# AIRDCL.net
KiCad netlist of a schematic drawn in EAGLE
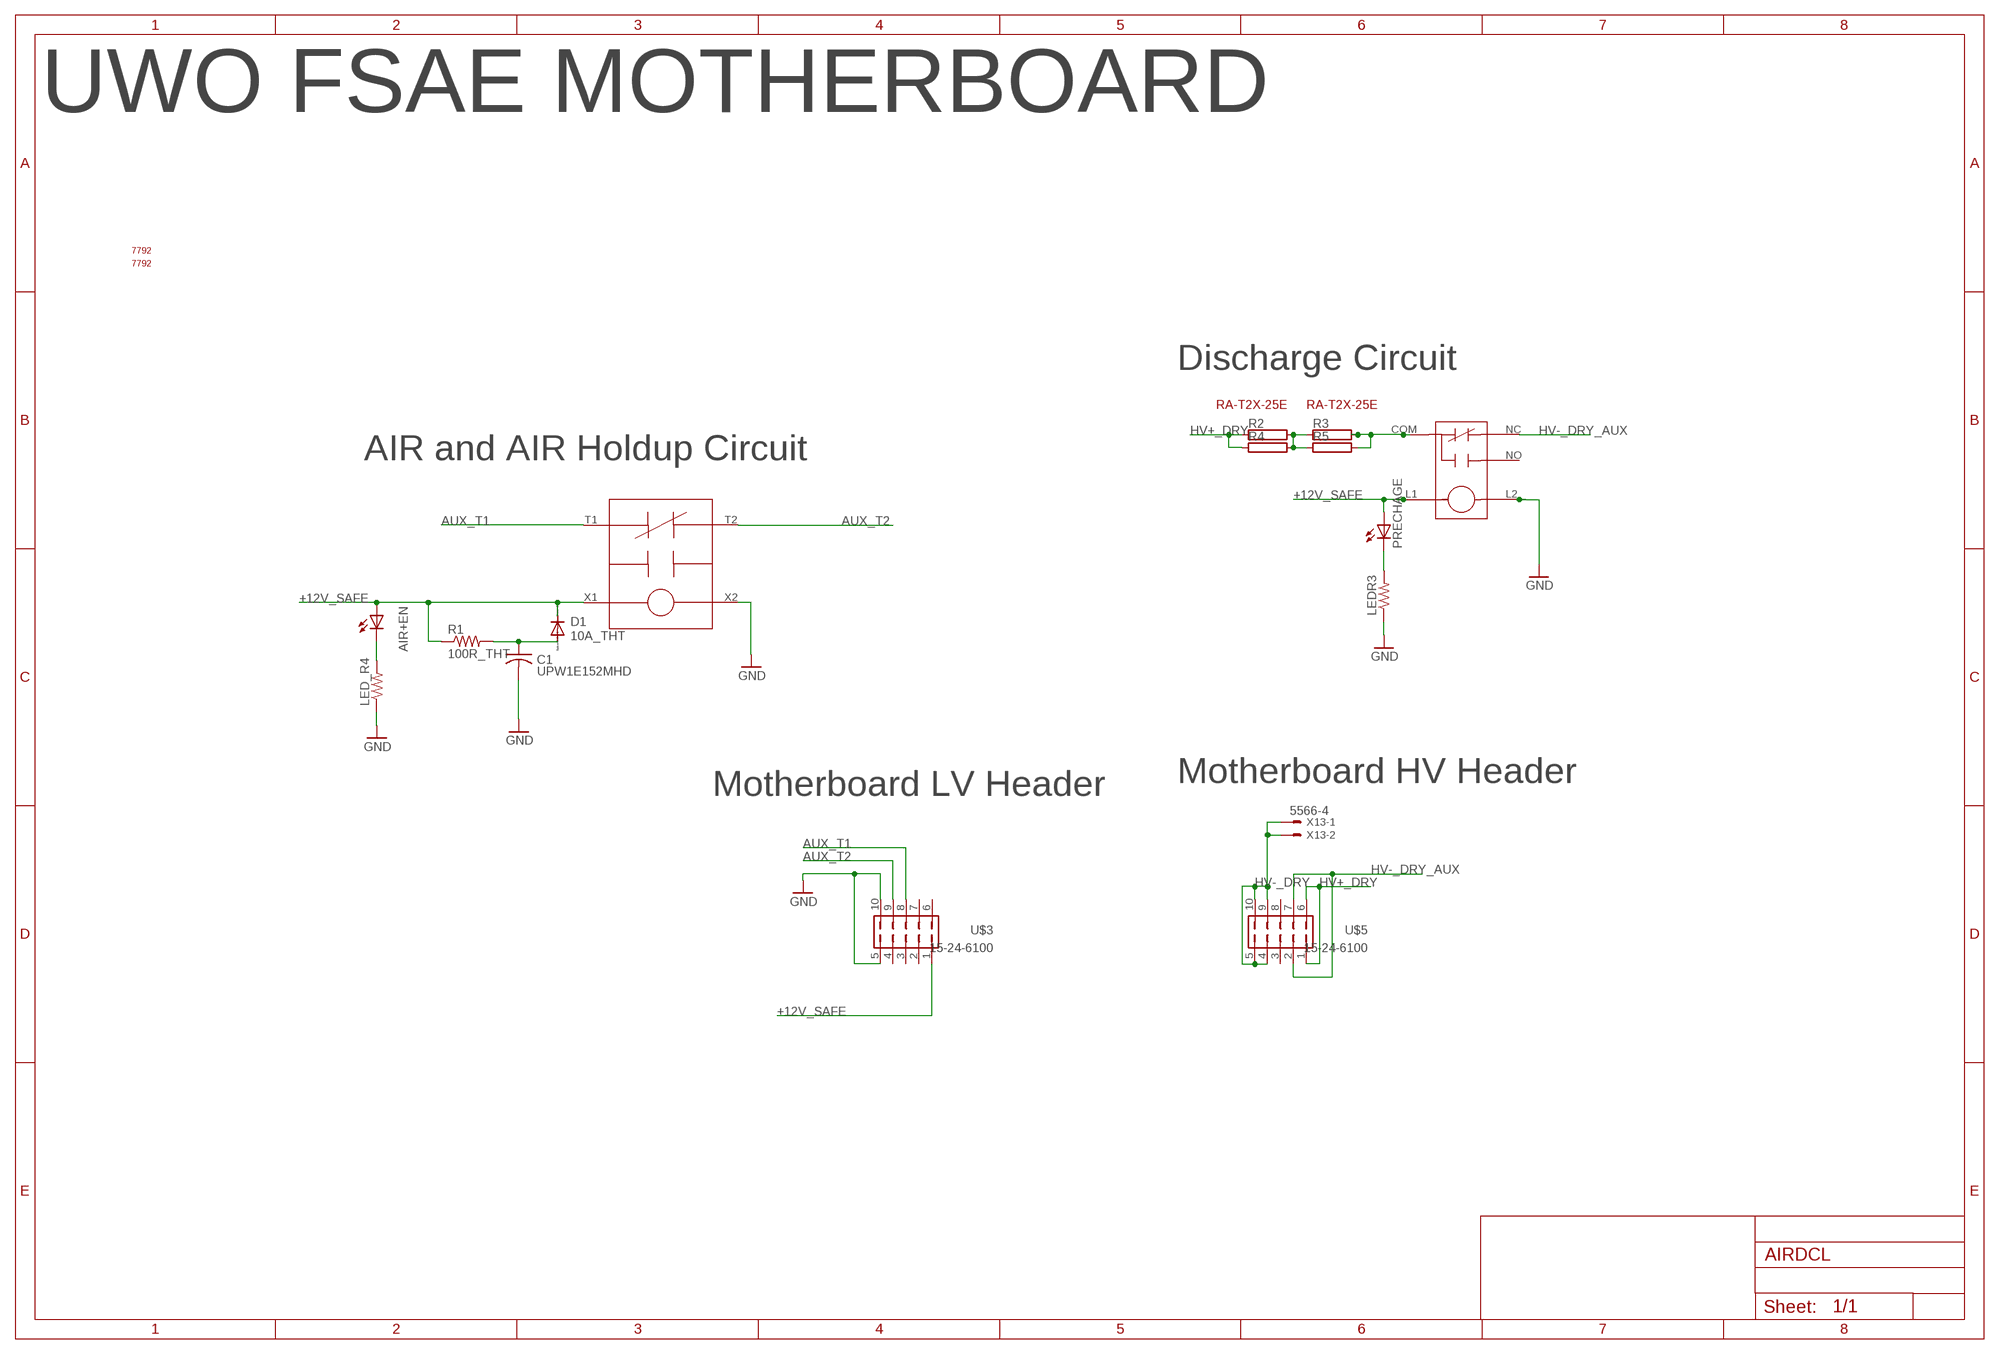
[diagram p0: schematic, sheet 1]

(export (version "E")
  (design (tool "Eeschema 10.0.6"))
  (components
    (comp (ref "AIR+EN")
      (value "LEDCHIPLED_0805")
      (footprint "eagle-import:CHIPLED_0805")
      (libsource (lib "eagle-import") (part "LEDCHIPLED_0805"))
    )
    (comp (ref "C1")
      (value "UPW1E152MHD")
      (footprint "eagle-import:CAPPRD750W65D1800H3700B")
      (libsource (lib "eagle-import") (part "AIR_HOLDUP_CAP"))
    )
    (comp (ref "D1")
      (value "10A_THT")
      (footprint "eagle-import:DIOAD1570W120L850D500B")
      (libsource (lib "eagle-import") (part "AIR_HOLDUP_DIODE"))
    )
    (comp (ref "LEDR3")
      (value "R-US_R0805")
      (footprint "eagle-import:R0805")
      (libsource (lib "eagle-import") (part "R-US_R0805"))
    )
    (comp (ref "LED_R4")
      (value "R-US_R0805")
      (footprint "eagle-import:R0805")
      (libsource (lib "eagle-import") (part "R-US_R0805"))
    )
    (comp (ref "PRECHAGE")
      (value "LEDCHIPLED_0805")
      (footprint "eagle-import:CHIPLED_0805")
      (libsource (lib "eagle-import") (part "LEDCHIPLED_0805"))
    )
    (comp (ref "R1")
      (value "100R_THT")
      (footprint "eagle-import:RESAD976W63L650D250B")
      (libsource (lib "eagle-import") (part "AIR_HOLDUP_RESISTOR"))
    )
    (comp (ref "R2")
      (value "RMG100-V")
      (footprint "eagle-import:TO-247-2V")
      (libsource (lib "eagle-import") (part "RMG100-V"))
    )
    (comp (ref "R3")
      (value "RMG100-V")
      (footprint "eagle-import:TO-247-2V")
      (libsource (lib "eagle-import") (part "RMG100-V"))
    )
    (comp (ref "R4")
      (value "RMG100-V")
      (footprint "eagle-import:TO-247-2V")
      (libsource (lib "eagle-import") (part "RMG100-V"))
    )
    (comp (ref "R5")
      (value "RMG100-V")
      (footprint "eagle-import:TO-247-2V")
      (libsource (lib "eagle-import") (part "RMG100-V"))
    )
    (comp (ref "U$1")
      (value "GV245BPB")
      (footprint "eagle-import:GV224")
      (libsource (lib "eagle-import") (part "GV224"))
    )
    (comp (ref "U$2")
      (value "7792")
      (footprint "eagle-import:7792")
      (libsource (lib "eagle-import") (part "7792"))
    )
    (comp (ref "U$3")
      (value "15-24-6100")
      (footprint "eagle-import:15-24-6100")
      (libsource (lib "eagle-import") (part "15-24-6100"))
    )
    (comp (ref "U$4")
      (value "G81C335")
      (footprint "eagle-import:G81C335")
      (libsource (lib "eagle-import") (part "G81C335"))
    )
    (comp (ref "U$5")
      (value "15-24-6100")
      (footprint "eagle-import:15-24-6100")
      (libsource (lib "eagle-import") (part "15-24-6100"))
    )
    (comp (ref "U$6")
      (value "7792")
      (footprint "eagle-import:7792")
      (libsource (lib "eagle-import") (part "7792"))
    )
    (comp (ref "U$8")
      (value "RA-T2X-25E")
      (footprint "eagle-import:RA-T2X-25E")
      (libsource (lib "eagle-import") (part "RA-T2X-25E"))
    )
    (comp (ref "U$9")
      (value "RA-T2X-25E")
      (footprint "eagle-import:RA-T2X-25E")
      (libsource (lib "eagle-import") (part "RA-T2X-25E"))
    )
    (comp (ref "X13")
      (value "5566-4")
      (footprint "eagle-import:5566-4")
      (fields (field (name "MF") "MOLEX"))
      (libsource (lib "eagle-import") (part "5566-4"))
    )
  )
  (nets
    (net (code "1") (name "/+12V_SAFE") (class "Default")
      (node (ref "AIR+EN") (pin "A") (pinfunction "A_A") (pintype "passive"))
      (node (ref "D1") (pin "1") (pinfunction "C_1") (pintype "passive"))
      (node (ref "PRECHAGE") (pin "A") (pinfunction "A_A") (pintype "passive"))
      (node (ref "R1") (pin "1") (pinfunction "1_1") (pintype "passive"))
      (node (ref "U$1") (pin "X1") (pinfunction "X1_X1") (pintype "bidirectional"))
      (node (ref "U$3") (pin "1") (pinfunction "1_1") (pintype "passive"))
      (node (ref "U$4") (pin "L1") (pinfunction "L1_L1") (pintype "bidirectional"))
    )
    (net (code "2") (name "/AUX_T1") (class "Default")
      (node (ref "U$1") (pin "T1") (pinfunction "T1_T1") (pintype "bidirectional"))
      (node (ref "U$3") (pin "8") (pinfunction "8_8") (pintype "passive"))
    )
    (net (code "3") (name "/AUX_T2") (class "Default")
      (node (ref "U$1") (pin "T2") (pinfunction "T2_T2") (pintype "bidirectional"))
      (node (ref "U$3") (pin "9") (pinfunction "9_9") (pintype "passive"))
    )
    (net (code "4") (name "/HV+_DRY") (class "Default")
      (node (ref "R2") (pin "1") (pinfunction "1_1") (pintype "passive"))
      (node (ref "R4") (pin "1") (pinfunction "1_1") (pintype "passive"))
      (node (ref "U$5") (pin "1") (pinfunction "1_1") (pintype "passive"))
      (node (ref "U$5") (pin "6") (pinfunction "6_6") (pintype "passive"))
    )
    (net (code "5") (name "/HV-_DRY") (class "Default")
      (node (ref "U$5") (pin "10") (pinfunction "10_10") (pintype "passive"))
      (node (ref "U$5") (pin "4") (pinfunction "4_4") (pintype "passive"))
      (node (ref "U$5") (pin "5") (pinfunction "5_5") (pintype "passive"))
      (node (ref "U$5") (pin "9") (pinfunction "9_9") (pintype "passive"))
      (node (ref "X13") (pin "1") (pinfunction "S_1") (pintype "passive"))
      (node (ref "X13") (pin "2") (pinfunction "S_2") (pintype "passive"))
    )
    (net (code "6") (name "/HV-_DRY_AUX") (class "Default")
      (node (ref "U$4") (pin "NC") (pinfunction "NC_NC") (pintype "bidirectional"))
      (node (ref "U$5") (pin "2") (pinfunction "2_2") (pintype "passive"))
      (node (ref "U$5") (pin "7") (pinfunction "7_7") (pintype "passive"))
    )
    (net (code "7") (name "GND") (class "Default")
      (node (ref "C1") (pin "2") (pinfunction "2_2") (pintype "passive"))
      (node (ref "LEDR3") (pin "1") (pinfunction "1_1") (pintype "passive"))
      (node (ref "LED_R4") (pin "1") (pinfunction "1_1") (pintype "passive"))
      (node (ref "U$1") (pin "X2") (pinfunction "X2_X2") (pintype "bidirectional"))
      (node (ref "U$3") (pin "10") (pinfunction "10_10") (pintype "passive"))
      (node (ref "U$3") (pin "5") (pinfunction "5_5") (pintype "passive"))
      (node (ref "U$4") (pin "L2") (pinfunction "L2_L2") (pintype "bidirectional"))
    )
    (net (code "8") (name "Net-(AIR+EN-PadC)") (class "Default")
      (node (ref "AIR+EN") (pin "C") (pinfunction "C_C") (pintype "passive"))
      (node (ref "LED_R4") (pin "2") (pinfunction "2_2") (pintype "passive"))
    )
    (net (code "9") (name "Net-(D1-A)") (class "Default")
      (node (ref "C1") (pin "1") (pinfunction "1_1") (pintype "passive"))
      (node (ref "D1") (pin "2") (pinfunction "A_2") (pintype "passive"))
      (node (ref "R1") (pin "2") (pinfunction "2_2") (pintype "passive"))
    )
    (net (code "10") (name "Net-(LEDR3-Pad2)") (class "Default")
      (node (ref "LEDR3") (pin "2") (pinfunction "2_2") (pintype "passive"))
      (node (ref "PRECHAGE") (pin "C") (pinfunction "C_C") (pintype "passive"))
    )
    (net (code "11") (name "Net-(R2-Pad2)") (class "Default")
      (node (ref "R2") (pin "2") (pinfunction "2_2") (pintype "passive"))
      (node (ref "R3") (pin "1") (pinfunction "1_1") (pintype "passive"))
      (node (ref "R4") (pin "2") (pinfunction "2_2") (pintype "passive"))
      (node (ref "R5") (pin "1") (pinfunction "1_1") (pintype "passive"))
    )
    (net (code "12") (name "Net-(R3-Pad2)") (class "Default")
      (node (ref "R3") (pin "2") (pinfunction "2_2") (pintype "passive"))
      (node (ref "R5") (pin "2") (pinfunction "2_2") (pintype "passive"))
      (node (ref "U$4") (pin "COM") (pinfunction "COM_COM") (pintype "bidirectional"))
    )
    (net (code "13") (name "unconnected-(U$3-Pad2)") (class "Default")
      (node (ref "U$3") (pin "2") (pinfunction "2_2") (pintype "passive"))
    )
    (net (code "14") (name "unconnected-(U$3-Pad3)") (class "Default")
      (node (ref "U$3") (pin "3") (pinfunction "3_3") (pintype "passive"))
    )
    (net (code "15") (name "unconnected-(U$3-Pad4)") (class "Default")
      (node (ref "U$3") (pin "4") (pinfunction "4_4") (pintype "passive"))
    )
    (net (code "16") (name "unconnected-(U$3-Pad6)") (class "Default")
      (node (ref "U$3") (pin "6") (pinfunction "6_6") (pintype "passive"))
    )
    (net (code "17") (name "unconnected-(U$3-Pad7)") (class "Default")
      (node (ref "U$3") (pin "7") (pinfunction "7_7") (pintype "passive"))
    )
    (net (code "18") (name "unconnected-(U$4-PadNO)") (class "Default")
      (node (ref "U$4") (pin "NO") (pinfunction "NO_NO") (pintype "bidirectional"))
    )
    (net (code "19") (name "unconnected-(U$5-Pad3)") (class "Default")
      (node (ref "U$5") (pin "3") (pinfunction "3_3") (pintype "passive"))
    )
    (net (code "20") (name "unconnected-(U$5-Pad8)") (class "Default")
      (node (ref "U$5") (pin "8") (pinfunction "8_8") (pintype "passive"))
    )
  )
)
